# relay-unit.net
KiCad netlist of a schematic drawn in EAGLE
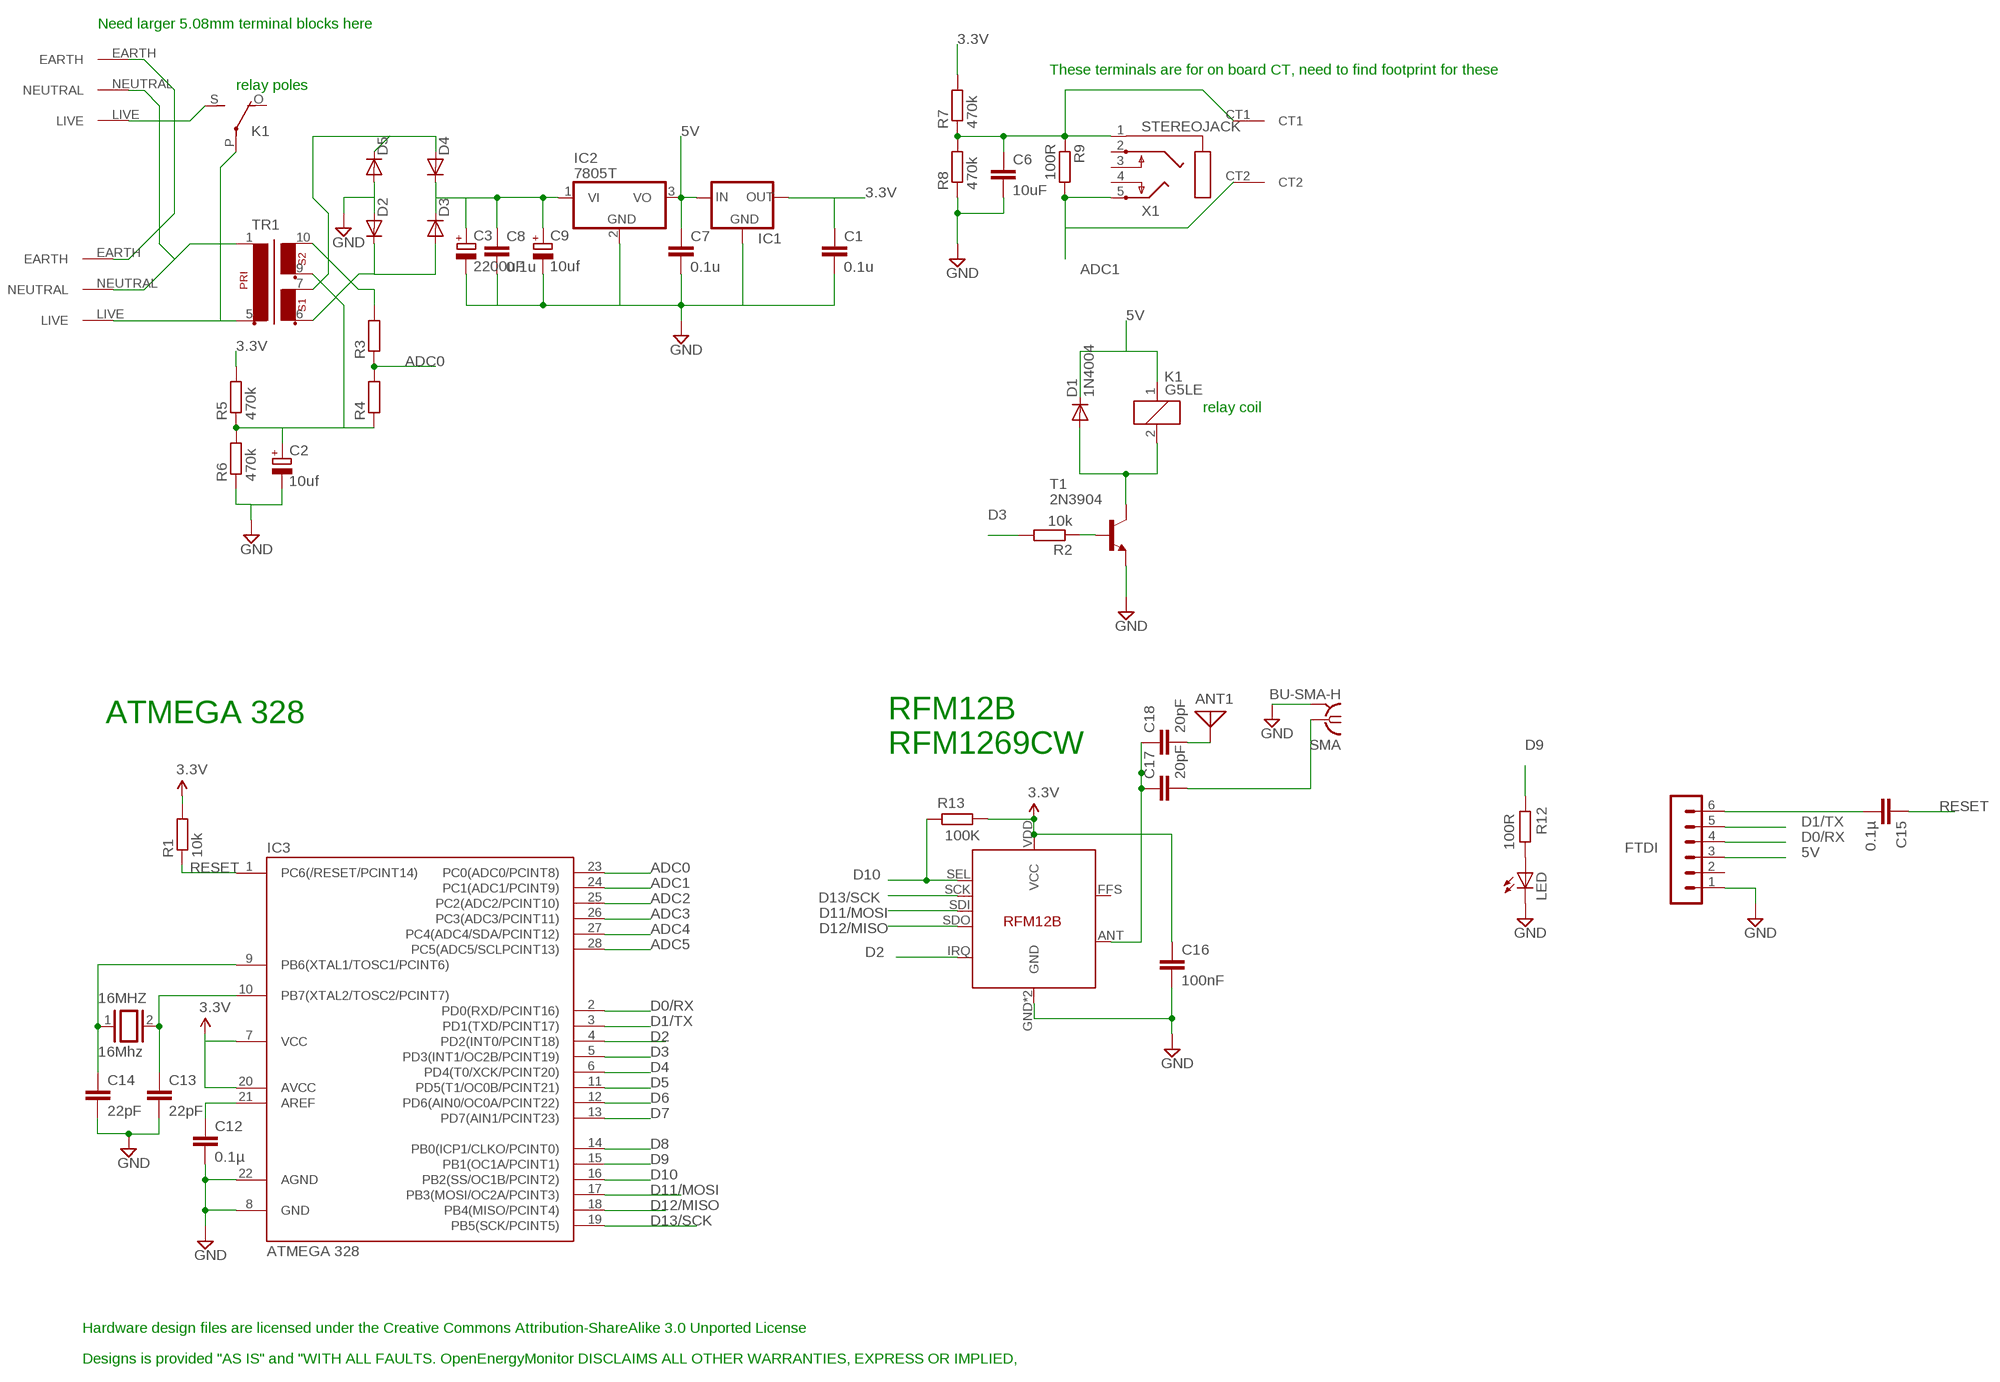
[diagram p0: schematic, sheet 1]

(export (version "E")
  (design (tool "Eeschema 10.0.6"))
  (components
    (comp (ref "16MHZ")
      (value "16Mhz")
      (footprint "eagle-import:QS")
      (libsource (lib "eagle-import") (part "XTAL/S"))
    )
    (comp (ref "ANT1")
      (value "ANTENNA")
      (footprint "eagle-import:PAD-01")
      (libsource (lib "eagle-import") (part "ANTENNA"))
    )
    (comp (ref "C1")
      (value "0.1u")
      (footprint "eagle-import:C025-024X044")
      (libsource (lib "eagle-import") (part "C-EU025-024X044"))
    )
    (comp (ref "C2")
      (value "10uf")
      (footprint "eagle-import:E1,8-4")
      (libsource (lib "eagle-import") (part "CPOL-EUE1.8-4"))
    )
    (comp (ref "C3")
      (value "2200uF")
      (footprint "eagle-import:E5-13")
      (libsource (lib "eagle-import") (part "CPOL-EUE5-13"))
    )
    (comp (ref "C6")
      (value "10uF")
      (footprint "eagle-import:C025-024X044")
      (libsource (lib "eagle-import") (part "C-EU025-024X044"))
    )
    (comp (ref "C7")
      (value "0.1u")
      (footprint "eagle-import:C025-024X044")
      (libsource (lib "eagle-import") (part "C-EU025-024X044"))
    )
    (comp (ref "C8")
      (value "0.1u")
      (footprint "eagle-import:C025-024X044")
      (libsource (lib "eagle-import") (part "C-EU025-024X044"))
    )
    (comp (ref "C9")
      (value "10uf")
      (footprint "eagle-import:E1,8-4")
      (libsource (lib "eagle-import") (part "CPOL-EUE1.8-4"))
    )
    (comp (ref "C12")
      (value "0.1µ")
      (footprint "eagle-import:C025-024X044")
      (libsource (lib "eagle-import") (part "C-EU025-024X044"))
    )
    (comp (ref "C13")
      (value "22pF")
      (footprint "eagle-import:C2.5-2")
      (libsource (lib "eagle-import") (part "C2.5/2"))
    )
    (comp (ref "C14")
      (value "22pF")
      (footprint "eagle-import:C2.5-2")
      (libsource (lib "eagle-import") (part "C2.5/2"))
    )
    (comp (ref "C15")
      (value "0.1µ")
      (footprint "eagle-import:C025-024X044")
      (libsource (lib "eagle-import") (part "C-EU025-024X044"))
    )
    (comp (ref "C16")
      (value "100nF")
      (footprint "eagle-import:C025-024X044")
      (libsource (lib "eagle-import") (part "C-EU025-024X044"))
    )
    (comp (ref "C17")
      (value "20pF")
      (footprint "eagle-import:C025-024X044")
      (libsource (lib "eagle-import") (part "C-EU025-024X044"))
    )
    (comp (ref "C18")
      (value "20pF")
      (footprint "eagle-import:C025-024X044")
      (libsource (lib "eagle-import") (part "C-EU025-024X044"))
    )
    (comp (ref "D1")
      (value "1N4004")
      (footprint "eagle-import:DO41-10")
      (libsource (lib "eagle-import") (part "1N4004"))
    )
    (comp (ref "D2")
      (value "1N4004")
      (footprint "eagle-import:DO41-10")
      (libsource (lib "eagle-import") (part "1N4004"))
    )
    (comp (ref "D3")
      (value "1N4004")
      (footprint "eagle-import:DO41-10")
      (libsource (lib "eagle-import") (part "1N4004"))
    )
    (comp (ref "D4")
      (value "1N4004")
      (footprint "eagle-import:DO41-10")
      (libsource (lib "eagle-import") (part "1N4004"))
    )
    (comp (ref "D5")
      (value "1N4004")
      (footprint "eagle-import:DO41-10")
      (libsource (lib "eagle-import") (part "1N4004"))
    )
    (comp (ref "FTDI")
      (value "FTDI")
      (footprint "eagle-import:MA06-1")
      (libsource (lib "eagle-import") (part "MA06-1"))
    )
    (comp (ref "IC1")
      (value "MCP1700TRI")
      (footprint "eagle-import:TO92")
      (libsource (lib "eagle-import") (part "MCP1700TRI"))
    )
    (comp (ref "IC2")
      (value "7805T")
      (footprint "eagle-import:TO220H")
      (libsource (lib "eagle-import") (part "78T05"))
    )
    (comp (ref "IC3")
      (value "ATMEGA 328")
      (footprint "eagle-import:DIL28-3")
      (libsource (lib "eagle-import") (part "ATMEGA48/88/168-PU"))
    )
    (comp (ref "K1")
      (value "G5LE")
      (footprint "eagle-import:G5LE")
      (libsource (lib "eagle-import") (part "G5LE"))
    )
    (comp (ref "LED")
      (value "LED3MM")
      (footprint "eagle-import:LED3MM")
      (libsource (lib "eagle-import") (part "LED3MM"))
    )
    (comp (ref "R1")
      (value "10k")
      (footprint "eagle-import:0204_7")
      (libsource (lib "eagle-import") (part "resistor_R-EU_0204/7"))
    )
    (comp (ref "R2")
      (value "10k")
      (footprint "eagle-import:0204_7")
      (libsource (lib "eagle-import") (part "R-EU_0204/7"))
    )
    (comp (ref "R3")
      (value "R-EU_0204/7")
      (footprint "eagle-import:0204_7")
      (libsource (lib "eagle-import") (part "R-EU_0204/7"))
    )
    (comp (ref "R4")
      (value "R-EU_0204/7")
      (footprint "eagle-import:0204_7")
      (libsource (lib "eagle-import") (part "R-EU_0204/7"))
    )
    (comp (ref "R5")
      (value "470k")
      (footprint "eagle-import:0204_7")
      (libsource (lib "eagle-import") (part "R-EU_0204/7"))
    )
    (comp (ref "R6")
      (value "470k")
      (footprint "eagle-import:0204_7")
      (libsource (lib "eagle-import") (part "R-EU_0204/7"))
    )
    (comp (ref "R7")
      (value "470k")
      (footprint "eagle-import:0204_7")
      (libsource (lib "eagle-import") (part "R-EU_0204/7"))
    )
    (comp (ref "R8")
      (value "470k")
      (footprint "eagle-import:0204_7")
      (libsource (lib "eagle-import") (part "R-EU_0204/7"))
    )
    (comp (ref "R9")
      (value "100R")
      (footprint "eagle-import:0204_7")
      (libsource (lib "eagle-import") (part "R-EU_0204/7"))
    )
    (comp (ref "R12")
      (value "100R")
      (footprint "eagle-import:0204_7")
      (libsource (lib "eagle-import") (part "R-EU_0204/7"))
    )
    (comp (ref "R13")
      (value "100K")
      (footprint "eagle-import:0204_7")
      (libsource (lib "eagle-import") (part "R-EU_0204/7"))
    )
    (comp (ref "SMA")
      (value "BU-SMA-H")
      (footprint "eagle-import:BU-SMA-H")
      (libsource (lib "eagle-import") (part "BU-SMA-H"))
    )
    (comp (ref "T1")
      (value "2N3904")
      (footprint "eagle-import:TO92")
      (libsource (lib "eagle-import") (part "2N3904"))
    )
    (comp (ref "TR1")
      (value "EI30-2")
      (footprint "eagle-import:EI30-2")
      (libsource (lib "eagle-import") (part "EI30-2"))
    )
    (comp (ref "U$1")
      (value "TESTTEST")
      (footprint "eagle-import:TEST")
      (libsource (lib "eagle-import") (part "TESTTEST"))
    )
    (comp (ref "U$2")
      (value "AC_IN")
      (footprint "eagle-import:AC_IN")
      (libsource (lib "eagle-import") (part "AC_IN"))
    )
    (comp (ref "U$3") (value "CT") (footprint "eagle-import:CT") (libsource (lib "eagle-import") (part "CT")))
    (comp (ref "U$14")
      (value "RFM12B")
      (footprint "eagle-import:RFM12B")
      (libsource (lib "eagle-import") (part "RFM12B"))
    )
    (comp (ref "X1")
      (value "STEREOJACK")
      (footprint "eagle-import:STX3100")
      (libsource (lib "eagle-import") (part "STEREOJACK"))
    )
  )
  (nets
    (net (code "1") (name "/5V") (class "Default")
      (node (ref "C7") (pin "1") (pinfunction "1_1") (pintype "passive"))
      (node (ref "D1") (pin "C") (pinfunction "C_C") (pintype "passive"))
      (node (ref "FTDI") (pin "3") (pinfunction "3_3") (pintype "passive"))
      (node (ref "IC1") (pin "2") (pinfunction "IN_2") (pintype "input"))
      (node (ref "IC2") (pin "3") (pinfunction "VO_3") (pintype "passive"))
      (node (ref "K1") (pin "1") (pinfunction "1_1") (pintype "passive"))
    )
    (net (code "2") (name "/ADC0") (class "Default")
      (node (ref "IC3") (pin "23") (pinfunction "PC0(ADC0/PCINT8)_23") (pintype "bidirectional"))
      (node (ref "R3") (pin "1") (pinfunction "1_1") (pintype "passive"))
      (node (ref "R4") (pin "2") (pinfunction "2_2") (pintype "passive"))
    )
    (net (code "3") (name "/ADC1") (class "Default")
      (node (ref "IC3") (pin "24") (pinfunction "PC1(ADC1/PCINT9)_24") (pintype "bidirectional"))
      (node (ref "R9") (pin "2") (pinfunction "2_2") (pintype "passive"))
      (node (ref "U$3") (pin "CT2") (pinfunction "CT2_CT2") (pintype "bidirectional"))
      (node (ref "X1") (pin "5") (pinfunction "5_5") (pintype "passive"))
    )
    (net (code "4") (name "/ADC2") (class "Default")
      (node (ref "IC3") (pin "25") (pinfunction "PC2(ADC2/PCINT10)_25") (pintype "bidirectional"))
    )
    (net (code "5") (name "/ADC3") (class "Default")
      (node (ref "IC3") (pin "26") (pinfunction "PC3(ADC3/PCINT11)_26") (pintype "bidirectional"))
    )
    (net (code "6") (name "/ADC4") (class "Default")
      (node (ref "IC3") (pin "27") (pinfunction "PC4(ADC4/SDA/PCINT12)_27") (pintype "bidirectional"))
    )
    (net (code "7") (name "/ADC5") (class "Default")
      (node (ref "IC3") (pin "28") (pinfunction "PC5(ADC5/SCLPCINT13)_28") (pintype "bidirectional"))
    )
    (net (code "8") (name "/D0{slash}RX") (class "Default")
      (node (ref "FTDI") (pin "4") (pinfunction "4_4") (pintype "passive"))
      (node (ref "IC3") (pin "2") (pinfunction "PD0(RXD/PCINT16)_2") (pintype "bidirectional"))
    )
    (net (code "9") (name "/D1{slash}TX") (class "Default")
      (node (ref "FTDI") (pin "5") (pinfunction "5_5") (pintype "passive"))
      (node (ref "IC3") (pin "3") (pinfunction "PD1(TXD/PCINT17)_3") (pintype "bidirectional"))
    )
    (net (code "10") (name "/D2") (class "Default")
      (node (ref "IC3") (pin "4") (pinfunction "PD2(INT0/PCINT18)_4") (pintype "bidirectional"))
      (node (ref "U$14") (pin "IRQ") (pinfunction "IRQ_IRQ") (pintype "open_collector"))
    )
    (net (code "11") (name "/D3") (class "Default")
      (node (ref "IC3") (pin "5") (pinfunction "PD3(INT1/OC2B/PCINT19)_5") (pintype "bidirectional"))
      (node (ref "R2") (pin "2") (pinfunction "2_2") (pintype "passive"))
    )
    (net (code "12") (name "/D4") (class "Default")
      (node (ref "IC3") (pin "6") (pinfunction "PD4(T0/XCK/PCINT20)_6") (pintype "bidirectional"))
    )
    (net (code "13") (name "/D5") (class "Default")
      (node (ref "IC3") (pin "11") (pinfunction "PD5(T1/OC0B/PCINT21)_11") (pintype "bidirectional"))
    )
    (net (code "14") (name "/D6") (class "Default")
      (node (ref "IC3") (pin "12") (pinfunction "PD6(AIN0/OC0A/PCINT22)_12") (pintype "bidirectional"))
    )
    (net (code "15") (name "/D7") (class "Default")
      (node (ref "IC3") (pin "13") (pinfunction "PD7(AIN1/PCINT23)_13") (pintype "bidirectional"))
    )
    (net (code "16") (name "/D8") (class "Default")
      (node (ref "IC3") (pin "14") (pinfunction "PB0(ICP1/CLKO/PCINT0)_14") (pintype "bidirectional"))
    )
    (net (code "17") (name "/D9") (class "Default")
      (node (ref "IC3") (pin "15") (pinfunction "PB1(OC1A/PCINT1)_15") (pintype "bidirectional"))
      (node (ref "R12") (pin "2") (pinfunction "2_2") (pintype "passive"))
    )
    (net (code "18") (name "/D10") (class "Default")
      (node (ref "IC3") (pin "16") (pinfunction "PB2(SS/OC1B/PCINT2)_16") (pintype "bidirectional"))
      (node (ref "R13") (pin "2") (pinfunction "2_2") (pintype "passive"))
      (node (ref "U$14") (pin "SEL") (pinfunction "SEL_SEL") (pintype "input"))
    )
    (net (code "19") (name "/D11{slash}MOSI") (class "Default")
      (node (ref "IC3") (pin "17") (pinfunction "PB3(MOSI/OC2A/PCINT3)_17") (pintype "bidirectional"))
      (node (ref "U$14") (pin "SDI") (pinfunction "SDI_SDI") (pintype "input"))
    )
    (net (code "20") (name "/D12{slash}MISO") (class "Default")
      (node (ref "IC3") (pin "18") (pinfunction "PB4(MISO/PCINT4)_18") (pintype "bidirectional"))
      (node (ref "U$14") (pin "SDO") (pinfunction "SDO_SDO") (pintype "output"))
    )
    (net (code "21") (name "/D13{slash}SCK") (class "Default")
      (node (ref "IC3") (pin "19") (pinfunction "PB5(SCK/PCINT5)_19") (pintype "bidirectional"))
      (node (ref "U$14") (pin "SCK") (pinfunction "SCK_SCK") (pintype "input"))
    )
    (net (code "22") (name "/RESET") (class "Default")
      (node (ref "C15") (pin "1") (pinfunction "1_1") (pintype "passive"))
      (node (ref "IC3") (pin "1") (pinfunction "PC6(/RESET/PCINT14)_1") (pintype "bidirectional"))
      (node (ref "R1") (pin "1") (pinfunction "1_1") (pintype "passive"))
    )
    (net (code "23") (name "3.3V") (class "Default")
      (node (ref "C1") (pin "1") (pinfunction "1_1") (pintype "passive"))
      (node (ref "C16") (pin "1") (pinfunction "1_1") (pintype "passive"))
      (node (ref "IC1") (pin "3") (pinfunction "OUT_3") (pintype "passive"))
      (node (ref "IC3") (pin "20") (pinfunction "AVCC_20") (pintype "passive"))
      (node (ref "IC3") (pin "7") (pinfunction "VCC_7") (pintype "power_in"))
      (node (ref "R1") (pin "2") (pinfunction "2_2") (pintype "passive"))
      (node (ref "R13") (pin "1") (pinfunction "1_1") (pintype "passive"))
      (node (ref "R5") (pin "2") (pinfunction "2_2") (pintype "passive"))
      (node (ref "R7") (pin "2") (pinfunction "2_2") (pintype "passive"))
      (node (ref "U$14") (pin "VDD") (pinfunction "VCC_VDD") (pintype "power_in"))
    )
    (net (code "24") (name "GND") (class "Default")
      (node (ref "C1") (pin "2") (pinfunction "2_2") (pintype "passive"))
      (node (ref "C12") (pin "2") (pinfunction "2_2") (pintype "passive"))
      (node (ref "C13") (pin "2") (pinfunction "2_2") (pintype "passive"))
      (node (ref "C14") (pin "2") (pinfunction "2_2") (pintype "passive"))
      (node (ref "C16") (pin "2") (pinfunction "2_2") (pintype "passive"))
      (node (ref "C2") (pin "-") (pinfunction "-_-") (pintype "passive"))
      (node (ref "C3") (pin "-") (pinfunction "-_-") (pintype "passive"))
      (node (ref "C6") (pin "2") (pinfunction "2_2") (pintype "passive"))
      (node (ref "C7") (pin "2") (pinfunction "2_2") (pintype "passive"))
      (node (ref "C8") (pin "2") (pinfunction "2_2") (pintype "passive"))
      (node (ref "C9") (pin "-") (pinfunction "-_-") (pintype "passive"))
      (node (ref "D2") (pin "A") (pinfunction "A_A") (pintype "passive"))
      (node (ref "D5") (pin "A") (pinfunction "A_A") (pintype "passive"))
      (node (ref "FTDI") (pin "1") (pinfunction "1_1") (pintype "passive"))
      (node (ref "IC1") (pin "1") (pinfunction "GND_1") (pintype "input"))
      (node (ref "IC2") (pin "2") (pinfunction "GND_2") (pintype "passive"))
      (node (ref "IC3") (pin "22") (pinfunction "AGND_22") (pintype "power_in"))
      (node (ref "IC3") (pin "8") (pinfunction "GND_8") (pintype "power_in"))
      (node (ref "LED") (pin "K") (pinfunction "C_K") (pintype "passive"))
      (node (ref "R6") (pin "1") (pinfunction "1_1") (pintype "passive"))
      (node (ref "R8") (pin "1") (pinfunction "1_1") (pintype "passive"))
      (node (ref "SMA") (pin "2") (pinfunction "2_2") (pintype "passive"))
      (node (ref "SMA") (pin "3") (pinfunction "2_3") (pintype "passive"))
      (node (ref "SMA") (pin "4") (pinfunction "2_4") (pintype "passive"))
      (node (ref "SMA") (pin "5") (pinfunction "2_5") (pintype "passive"))
      (node (ref "T1") (pin "3") (pinfunction "E_3") (pintype "passive"))
      (node (ref "U$14") (pin "GND") (pinfunction "GND_GND") (pintype "power_in"))
      (node (ref "U$14") (pin "P$12") (pinfunction "GND_P$12") (pintype "power_in"))
    )
    (net (code "25") (name "Net-(ANT1-Pad1)") (class "Default")
      (node (ref "ANT1") (pin "1") (pinfunction "1_1") (pintype "output"))
      (node (ref "C18") (pin "2") (pinfunction "2_2") (pintype "passive"))
    )
    (net (code "26") (name "Net-(C6-Pad1)") (class "Default")
      (node (ref "C6") (pin "1") (pinfunction "1_1") (pintype "passive"))
      (node (ref "R7") (pin "1") (pinfunction "1_1") (pintype "passive"))
      (node (ref "R8") (pin "2") (pinfunction "2_2") (pintype "passive"))
      (node (ref "R9") (pin "1") (pinfunction "1_1") (pintype "passive"))
      (node (ref "U$3") (pin "CT1") (pinfunction "CT1_CT1") (pintype "bidirectional"))
      (node (ref "X1") (pin "1") (pinfunction "1_1") (pintype "passive"))
    )
    (net (code "27") (name "Net-(C15-Pad2)") (class "Default")
      (node (ref "C15") (pin "2") (pinfunction "2_2") (pintype "passive"))
      (node (ref "FTDI") (pin "6") (pinfunction "6_6") (pintype "passive"))
    )
    (net (code "28") (name "Net-(C17-Pad1)") (class "Default")
      (node (ref "C17") (pin "1") (pinfunction "1_1") (pintype "passive"))
      (node (ref "C18") (pin "1") (pinfunction "1_1") (pintype "passive"))
      (node (ref "U$14") (pin "ANT") (pinfunction "ANT_ANT") (pintype "passive"))
    )
    (net (code "29") (name "Net-(C17-Pad2)") (class "Default")
      (node (ref "C17") (pin "2") (pinfunction "2_2") (pintype "passive"))
      (node (ref "SMA") (pin "1") (pinfunction "1_1") (pintype "passive"))
    )
    (net (code "30") (name "Net-(IC2-VI)") (class "Default")
      (node (ref "C3") (pin "+") (pinfunction "+_+") (pintype "passive"))
      (node (ref "C8") (pin "1") (pinfunction "1_1") (pintype "passive"))
      (node (ref "C9") (pin "+") (pinfunction "+_+") (pintype "passive"))
      (node (ref "D3") (pin "C") (pinfunction "C_C") (pintype "passive"))
      (node (ref "D4") (pin "C") (pinfunction "C_C") (pintype "passive"))
      (node (ref "IC2") (pin "1") (pinfunction "VI_1") (pintype "input"))
    )
    (net (code "31") (name "Net-(IC3-AREF)") (class "Default")
      (node (ref "C12") (pin "1") (pinfunction "1_1") (pintype "passive"))
      (node (ref "IC3") (pin "21") (pinfunction "AREF_21") (pintype "passive"))
    )
    (net (code "32") (name "Net-(IC3-PB6(XTAL1{slash}TOSC1{slash}PCINT6))") (class "Default")
      (node (ref "16MHZ") (pin "1") (pinfunction "1_1") (pintype "passive"))
      (node (ref "C14") (pin "1") (pinfunction "1_1") (pintype "passive"))
      (node (ref "IC3") (pin "9") (pinfunction "PB6(XTAL1/TOSC1/PCINT6)_9") (pintype "bidirectional"))
    )
    (net (code "33") (name "Net-(IC3-PB7(XTAL2{slash}TOSC2{slash}PCINT7))") (class "Default")
      (node (ref "16MHZ") (pin "2") (pinfunction "2_2") (pintype "passive"))
      (node (ref "C13") (pin "1") (pinfunction "1_1") (pintype "passive"))
      (node (ref "IC3") (pin "10") (pinfunction "PB7(XTAL2/TOSC2/PCINT7)_10") (pintype "bidirectional"))
    )
    (net (code "34") (name "Net-(K1-PadS)") (class "Default")
      (node (ref "K1") (pin "S") (pinfunction "S_S") (pintype "passive"))
      (node (ref "U$1") (pin "LIVE") (pinfunction "LIVE_LIVE") (pintype "input"))
    )
    (net (code "35") (name "Net-(LED-PadA)") (class "Default")
      (node (ref "LED") (pin "A") (pinfunction "A_A") (pintype "passive"))
      (node (ref "R12") (pin "1") (pinfunction "1_1") (pintype "passive"))
    )
    (net (code "36") (name "Net-(T1-B)") (class "Default")
      (node (ref "R2") (pin "1") (pinfunction "1_1") (pintype "passive"))
      (node (ref "T1") (pin "2") (pinfunction "B_2") (pintype "passive"))
    )
    (net (code "37") (name "Net-(T1-C)") (class "Default")
      (node (ref "D1") (pin "A") (pinfunction "A_A") (pintype "passive"))
      (node (ref "K1") (pin "2") (pinfunction "2_2") (pintype "passive"))
      (node (ref "T1") (pin "1") (pinfunction "C_1") (pintype "passive"))
    )
    (net (code "38") (name "Net-(TR1-2)") (class "Default")
      (node (ref "K1") (pin "P") (pinfunction "P_P") (pintype "passive"))
      (node (ref "TR1") (pin "5") (pinfunction "2_5") (pintype "passive"))
      (node (ref "U$2") (pin "LIVE") (pinfunction "LIVE_LIVE") (pintype "bidirectional"))
    )
    (net (code "39") (name "Net-(TR1-3)") (class "Default")
      (node (ref "D2") (pin "C") (pinfunction "C_C") (pintype "passive"))
      (node (ref "D3") (pin "A") (pinfunction "A_A") (pintype "passive"))
      (node (ref "TR1") (pin "6") (pinfunction "3_6") (pintype "passive"))
    )
    (net (code "40") (name "Net-(TR1-4)") (class "Default")
      (node (ref "D4") (pin "A") (pinfunction "A_A") (pintype "passive"))
      (node (ref "D5") (pin "C") (pinfunction "C_C") (pintype "passive"))
      (node (ref "TR1") (pin "7") (pinfunction "4_7") (pintype "passive"))
    )
    (net (code "41") (name "Net-(TR1-5)") (class "Default")
      (node (ref "C2") (pin "+") (pinfunction "+_+") (pintype "passive"))
      (node (ref "R4") (pin "1") (pinfunction "1_1") (pintype "passive"))
      (node (ref "R5") (pin "1") (pinfunction "1_1") (pintype "passive"))
      (node (ref "R6") (pin "2") (pinfunction "2_2") (pintype "passive"))
      (node (ref "TR1") (pin "9") (pinfunction "5_9") (pintype "passive"))
    )
    (net (code "42") (name "Net-(TR1-6)") (class "Default")
      (node (ref "R3") (pin "2") (pinfunction "2_2") (pintype "passive"))
      (node (ref "TR1") (pin "10") (pinfunction "6_10") (pintype "passive"))
    )
    (net (code "43") (name "Net-(TR1-Pad1)") (class "Default")
      (node (ref "TR1") (pin "1") (pinfunction "1_1") (pintype "passive"))
      (node (ref "U$1") (pin "NEUTRAL") (pinfunction "NEUTRAL_NEUTRAL") (pintype "input"))
      (node (ref "U$2") (pin "NEUTRAL") (pinfunction "NEUTRAL_NEUTRAL") (pintype "bidirectional"))
    )
    (net (code "44") (name "Net-(U$1-PadEARTH)") (class "Default")
      (node (ref "U$1") (pin "EARTH") (pinfunction "EARTH_EARTH") (pintype "input"))
      (node (ref "U$2") (pin "EARTH") (pinfunction "EARTH_EARTH") (pintype "bidirectional"))
    )
    (net (code "45") (name "unconnected-(FTDI-Pad2)") (class "Default")
      (node (ref "FTDI") (pin "2") (pinfunction "2_2") (pintype "passive"))
    )
    (net (code "46") (name "unconnected-(K1-PadO)") (class "Default")
      (node (ref "K1") (pin "O") (pinfunction "O_O") (pintype "passive"))
    )
    (net (code "47") (name "unconnected-(U$14-PadFFS)") (class "Default")
      (node (ref "U$14") (pin "FFS") (pinfunction "FFS_FFS") (pintype "bidirectional"))
    )
    (net (code "48") (name "unconnected-(X1-Pad2)") (class "Default")
      (node (ref "X1") (pin "2") (pinfunction "2_2") (pintype "passive"))
    )
    (net (code "49") (name "unconnected-(X1-Pad3)") (class "Default")
      (node (ref "X1") (pin "3") (pinfunction "3_3") (pintype "passive"))
    )
    (net (code "50") (name "unconnected-(X1-Pad4)") (class "Default")
      (node (ref "X1") (pin "4") (pinfunction "4_4") (pintype "passive"))
    )
  )
)
